# RheoBoard_V8.net
KiCad netlist of a schematic drawn in Altium Designer
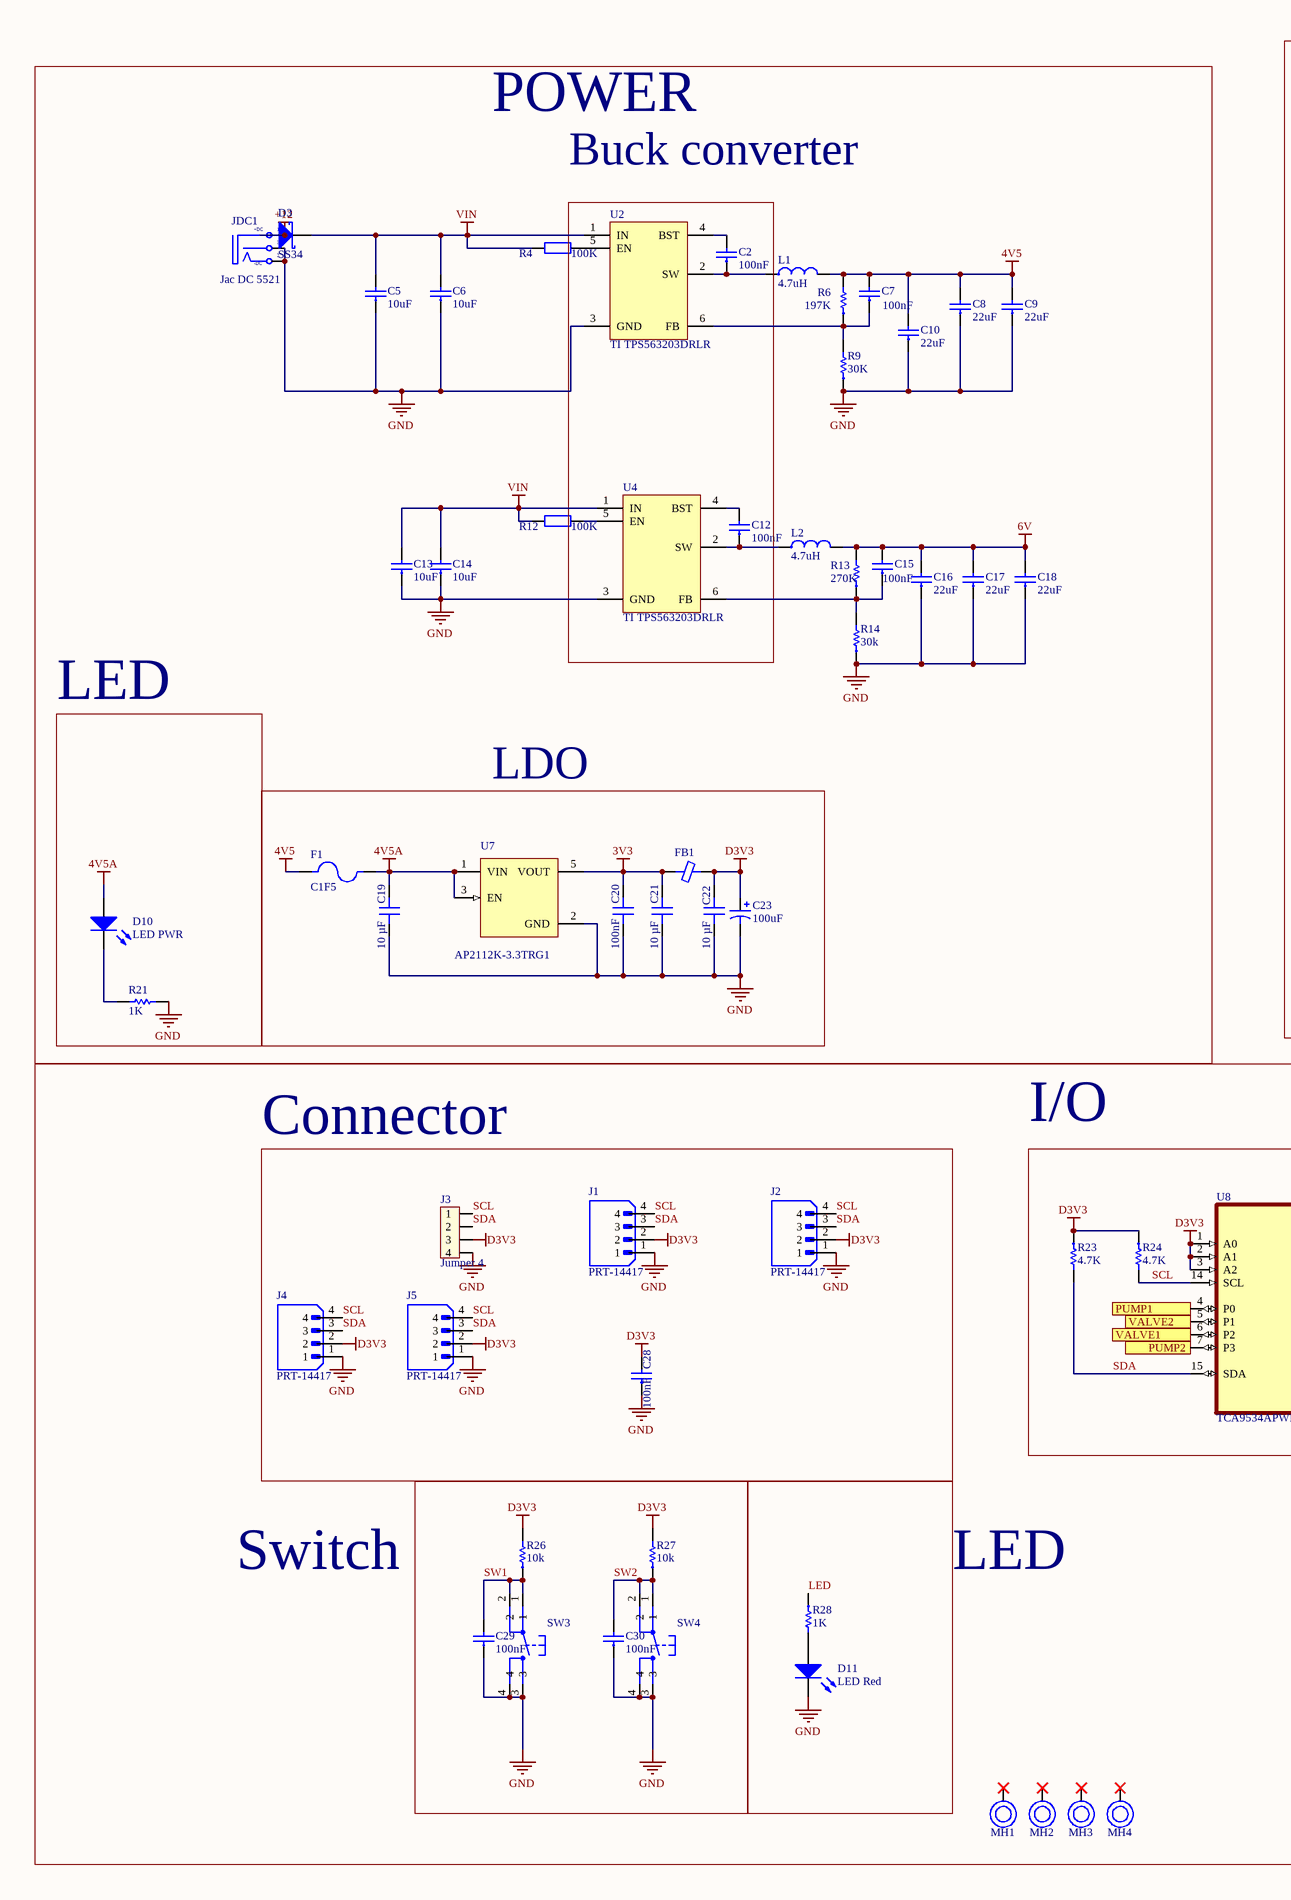
[diagram p0: RheoBoard_V8.SchDoc, left]
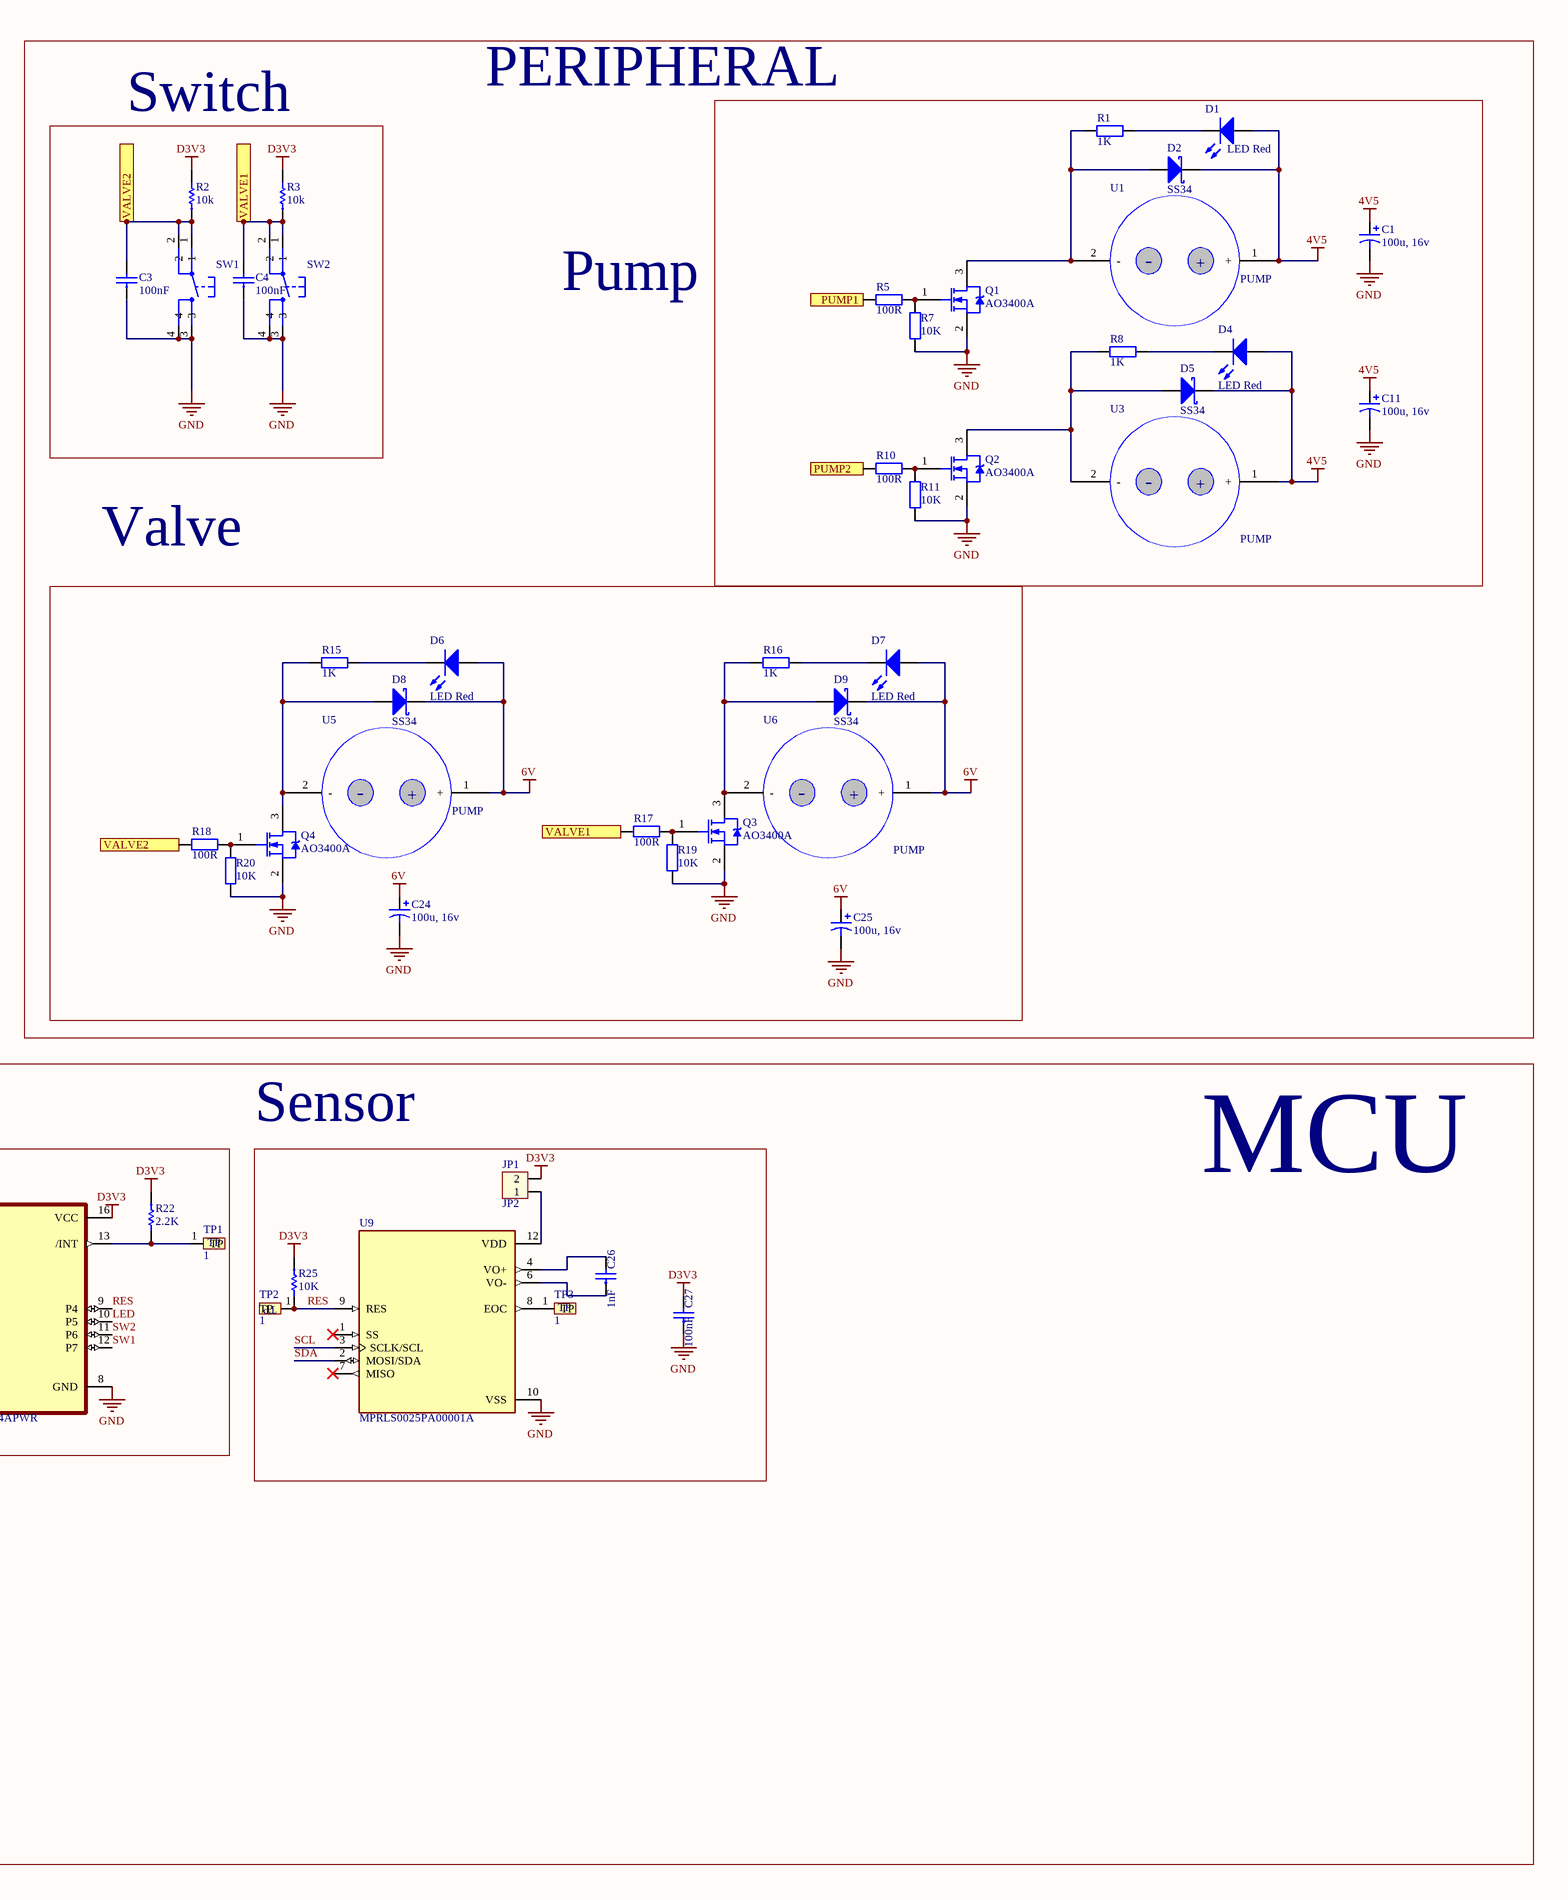
[diagram p1: RheoBoard_V8.SchDoc, right]

(export (version "E")
  (design (tool "Eeschema 10.0.6"))
  (components
    (comp (ref "C1")
      (value "100u, 16v")
      (footprint "CAPACITOR SIZE_D(D6.6)")
      (description "Nichicon Aluminum Cap 220uF 10V 20%")
      (fields (field (name "Comment") "CAP ALUM 100UF 20% 16V SMD"))
      (libsource (lib "capacitor") (part "UWT1C101MCL1GB"))
    )
    (comp (ref "C2")
      (value "100nF")
      (footprint "C0603")
      (description "CAP CER 100nF 10% 50V X7R 0603 SMD")
      (libsource (lib "2502-GMQLITE-MAIN") (part "CAPCER0001 100nF 10% 50V X7R 0603 SMD_1"))
    )
    (comp (ref "C3")
      (value "100nF")
      (footprint "C0603")
      (description "CAP CER 100nF 10% 50V X7R 0603 SMD")
      (libsource (lib "2502-GMQLITE-MAIN") (part "CAPCER0001 100nF 10% 50V X7R 0603 SMD"))
    )
    (comp (ref "C4")
      (value "100nF")
      (footprint "C0603")
      (description "CAP CER 100nF 10% 50V X7R 0603 SMD")
      (libsource (lib "2502-GMQLITE-MAIN") (part "CAPCER0001 100nF 10% 50V X7R 0603 SMD"))
    )
    (comp (ref "C5")
      (value "10uF")
      (footprint "CN-SMD-0603")
      (description "CAP CER 10uF 20% 6.3V X5R 0402 SMD")
      (libsource (lib "2502-GMQLITE-MAIN") (part "CAPCER0040 10uF 20% 6.3V X5R 0402 SMD"))
    )
    (comp (ref "C6")
      (value "10uF")
      (footprint "CN-SMD-0603")
      (description "CAP CER 10uF 20% 6.3V X5R 0402 SMD")
      (libsource (lib "2502-GMQLITE-MAIN") (part "CAPCER0040 10uF 20% 6.3V X5R 0402 SMD"))
    )
    (comp (ref "C7")
      (value "100nF")
      (footprint "C0603")
      (description "CAP CER 100nF 10% 50V X7R 0603 SMD")
      (libsource (lib "2502-GMQLITE-MAIN") (part "CAPCER0001 100nF 10% 50V X7R 0603 SMD"))
    )
    (comp (ref "C8")
      (value "22uF")
      (footprint "CN-SMD-0603")
      (description "CAP CER 10uF 20% 6.3V X5R 0402 SMD")
      (libsource (lib "2502-GMQLITE-MAIN") (part "CAPCER0040 10uF 20% 6.3V X5R 0402 SMD"))
    )
    (comp (ref "C9")
      (value "22uF")
      (footprint "CN-SMD-0603")
      (description "CAP CER 10uF 20% 6.3V X5R 0402 SMD")
      (libsource (lib "2502-GMQLITE-MAIN") (part "CAPCER0040 10uF 20% 6.3V X5R 0402 SMD"))
    )
    (comp (ref "C10")
      (value "22uF")
      (footprint "CN-SMD-0603")
      (description "CAP CER 10uF 20% 6.3V X5R 0402 SMD")
      (libsource (lib "2502-GMQLITE-MAIN") (part "CAPCER0040 10uF 20% 6.3V X5R 0402 SMD"))
    )
    (comp (ref "C11")
      (value "100u, 16v")
      (footprint "CAPACITOR SIZE_D(D6.6)")
      (description "Nichicon Aluminum Cap 220uF 10V 20%")
      (fields (field (name "Comment") "CAP ALUM 100UF 20% 16V SMD"))
      (libsource (lib "capacitor") (part "UWT1C101MCL1GB"))
    )
    (comp (ref "C12")
      (value "100nF")
      (footprint "C0603")
      (description "CAP CER 100nF 10% 50V X7R 0603 SMD")
      (libsource (lib "2502-GMQLITE-MAIN") (part "CAPCER0001 100nF 10% 50V X7R 0603 SMD_1"))
    )
    (comp (ref "C13")
      (value "10uF")
      (footprint "CN-SMD-0603")
      (description "CAP CER 10uF 20% 6.3V X5R 0402 SMD")
      (libsource (lib "2502-GMQLITE-MAIN") (part "CAPCER0040 10uF 20% 6.3V X5R 0402 SMD"))
    )
    (comp (ref "C14")
      (value "10uF")
      (footprint "CN-SMD-0603")
      (description "CAP CER 10uF 20% 6.3V X5R 0402 SMD")
      (libsource (lib "2502-GMQLITE-MAIN") (part "CAPCER0040 10uF 20% 6.3V X5R 0402 SMD"))
    )
    (comp (ref "C15")
      (value "100nF")
      (footprint "C0603")
      (description "CAP CER 100nF 10% 50V X7R 0603 SMD")
      (libsource (lib "2502-GMQLITE-MAIN") (part "CAPCER0001 100nF 10% 50V X7R 0603 SMD"))
    )
    (comp (ref "C16")
      (value "22uF")
      (footprint "CN-SMD-0603")
      (description "CAP CER 10uF 20% 6.3V X5R 0402 SMD")
      (libsource (lib "2502-GMQLITE-MAIN") (part "CAPCER0040 10uF 20% 6.3V X5R 0402 SMD"))
    )
    (comp (ref "C17")
      (value "22uF")
      (footprint "CN-SMD-0603")
      (description "CAP CER 10uF 20% 6.3V X5R 0402 SMD")
      (libsource (lib "2502-GMQLITE-MAIN") (part "CAPCER0040 10uF 20% 6.3V X5R 0402 SMD"))
    )
    (comp (ref "C18")
      (value "22uF")
      (footprint "CN-SMD-0603")
      (description "CAP CER 10uF 20% 6.3V X5R 0402 SMD")
      (libsource (lib "2502-GMQLITE-MAIN") (part "CAPCER0040 10uF 20% 6.3V X5R 0402 SMD"))
    )
    (comp (ref "C19")
      (value "10 µF")
      (footprint "C0603")
      (description "CAP0603 X7R 10UF 10% 10V")
      (fields
        (field (name "PART NUMBER") "GMC10X7R106K10NT")
        (field (name "MANUFACTURER") "Cal-Chip Electronics, Inc.")
      )
      (libsource (lib "Celestial Altium Library - altium_library") (part "Capacitor"))
    )
    (comp (ref "C20")
      (value "100nF")
      (footprint "C0603")
      (description "CAP0603 X7R 10UF 10% 10V")
      (fields
        (field (name "PART NUMBER") "GMC10X7R106K10NT")
        (field (name "MANUFACTURER") "Cal-Chip Electronics, Inc.")
      )
      (libsource (lib "Celestial Altium Library - altium_library") (part "Capacitor"))
    )
    (comp (ref "C21")
      (value "10 µF")
      (footprint "C0603")
      (description "CAP0603 X7R 10UF 10% 10V")
      (fields
        (field (name "PART NUMBER") "GMC10X7R106K10NT")
        (field (name "MANUFACTURER") "Cal-Chip Electronics, Inc.")
      )
      (libsource (lib "Celestial Altium Library - altium_library") (part "Capacitor"))
    )
    (comp (ref "C22")
      (value "10 µF")
      (footprint "C0603")
      (description "CAP0603 X7R 10UF 10% 10V")
      (fields
        (field (name "PART NUMBER") "GMC10X7R106K10NT")
        (field (name "MANUFACTURER") "Cal-Chip Electronics, Inc.")
      )
      (libsource (lib "Celestial Altium Library - altium_library") (part "Capacitor"))
    )
    (comp (ref "C23")
      (value "100uF")
      (footprint "CAPACITOR SIZE_D(D6.6)")
      (description "Nichicon Aluminum Cap 220uF 10V 20%")
      (fields (field (name "Comment") "CAP ALUM 100UF 20% 16V SMD"))
      (libsource (lib "capacitor") (part "UWT1C101MCL1GB"))
    )
    (comp (ref "C24")
      (value "100u, 16v")
      (footprint "CAPACITOR SIZE_D(D6.6)")
      (description "Nichicon Aluminum Cap 220uF 10V 20%")
      (fields (field (name "Comment") "CAP ALUM 100UF 20% 16V SMD"))
      (libsource (lib "capacitor") (part "UWT1C101MCL1GB"))
    )
    (comp (ref "C25")
      (value "100u, 16v")
      (footprint "CAPACITOR SIZE_D(D6.6)")
      (description "Nichicon Aluminum Cap 220uF 10V 20%")
      (fields (field (name "Comment") "CAP ALUM 100UF 20% 16V SMD"))
      (libsource (lib "capacitor") (part "UWT1C101MCL1GB"))
    )
    (comp (ref "C26")
      (value "1nF")
      (footprint "C0603")
      (description "CAP CER 100nF 10% 50V X7R 0603 SMD")
      (libsource (lib "2502-GMQLITE-MAIN") (part "CAPCER0001 100nF 10% 50V X7R 0603 SMD"))
    )
    (comp (ref "C27")
      (value "100nF")
      (footprint "C0603")
      (description "CAP CER 100nF 10% 50V X7R 0603 SMD")
      (libsource (lib "2502-GMQLITE-MAIN") (part "CAPCER0001 100nF 10% 50V X7R 0603 SMD"))
    )
    (comp (ref "C28")
      (value "100nF")
      (footprint "C0603")
      (description "CAP CER 100nF 10% 50V X7R 0603 SMD")
      (libsource (lib "2502-GMQLITE-MAIN") (part "CAPCER0001 100nF 10% 50V X7R 0603 SMD"))
    )
    (comp (ref "C29")
      (value "100nF")
      (footprint "C0603")
      (description "CAP CER 100nF 10% 50V X7R 0603 SMD")
      (libsource (lib "2502-GMQLITE-MAIN") (part "CAPCER0001 100nF 10% 50V X7R 0603 SMD"))
    )
    (comp (ref "C30")
      (value "100nF")
      (footprint "C0603")
      (description "CAP CER 100nF 10% 50V X7R 0603 SMD")
      (libsource (lib "2502-GMQLITE-MAIN") (part "CAPCER0001 100nF 10% 50V X7R 0603 SMD"))
    )
    (comp (ref "D1")
      (value "LED Red")
      (footprint "LED0603-R")
      (description "Lite-On LED Red 0603")
      (libsource (lib "diode") (part "LTST-C190KRKT"))
    )
    (comp (ref "D2")
      (value "SS34")
      (footprint "DO-214AC")
      (description "Schottky Diode 40V 3A SMA")
      (libsource (lib "diode") (part "SS34"))
    )
    (comp (ref "D3")
      (value "SS34")
      (footprint "DO-214AC")
      (description "Schottky Diode 40V 3A SMA")
      (libsource (lib "diode") (part "SS34"))
    )
    (comp (ref "D4")
      (value "LED Red")
      (footprint "LED0603-R")
      (description "Lite-On LED Red 0603")
      (libsource (lib "diode") (part "LTST-C190KRKT"))
    )
    (comp (ref "D5")
      (value "SS34")
      (footprint "DO-214AC")
      (description "Schottky Diode 40V 3A SMA")
      (libsource (lib "diode") (part "SS34"))
    )
    (comp (ref "D6")
      (value "LED Red")
      (footprint "LED0603-R")
      (description "Lite-On LED Red 0603")
      (libsource (lib "diode") (part "LTST-C190KRKT"))
    )
    (comp (ref "D7")
      (value "LED Red")
      (footprint "LED0603-R")
      (description "Lite-On LED Red 0603")
      (libsource (lib "diode") (part "LTST-C190KRKT"))
    )
    (comp (ref "D8")
      (value "SS34")
      (footprint "DO-214AC")
      (description "Schottky Diode 40V 3A SMA")
      (libsource (lib "diode") (part "SS34"))
    )
    (comp (ref "D9")
      (value "SS34")
      (footprint "DO-214AC")
      (description "Schottky Diode 40V 3A SMA")
      (libsource (lib "diode") (part "SS34"))
    )
    (comp (ref "D10")
      (value "LED PWR")
      (footprint "LED0603-R")
      (description "Lite-On LED Red 0603")
      (fields (field (name "Comment") "LED Red"))
      (libsource (lib "diode") (part "LTST-C190KRKT"))
    )
    (comp (ref "D11")
      (value "LED Red")
      (footprint "LED0603-R")
      (description "Lite-On LED Red 0603")
      (libsource (lib "diode") (part "LTST-C190KRKT"))
    )
    (comp (ref "F1")
      (value "C1F5")
      (footprint "FUSE C1F5")
      (description "Fuse Chip Fast Acting 5A 125V SMD Solder Pad 1206 3.2 X 1.58 X 0.63mm")
      (fields (field (name "MANUFACTURER") "Bel TRP"))
      (libsource (lib "POWER_PIN_CAMERA") (part "C1F5"))
    )
    (comp (ref "FB1")
      (value "330 Ohms @ 100 MHz")
      (footprint "L0603")
      (description "FERRITE BEAD 330 OHM 0603 1LN")
      (fields
        (field (name "PART NUMBER") "BLM18KG331SH1D")
        (field (name "MANUFACTURER") "Murata Electronics")
      )
      (libsource (lib "Celestial Altium Library - altium_library") (part "Ferrite Chip"))
    )
    (comp (ref "J1")
      (value "PRT-14417")
      (footprint "SPARKFUN_PRT-14417")
      (description "QWIIC JST CONNECTOR - SMD 4-PIN")
      (fields (field (name "MF") "SparkFun Electronics"))
      (libsource (lib "PRT-14417") (part "PRT-14417"))
    )
    (comp (ref "J2")
      (value "PRT-14417")
      (footprint "SPARKFUN_PRT-14417")
      (description "QWIIC JST CONNECTOR - SMD 4-PIN")
      (fields (field (name "MF") "SparkFun Electronics"))
      (libsource (lib "PRT-14417") (part "PRT-14417"))
    )
    (comp (ref "J3")
      (value "Jumper 4")
      (footprint "JP4")
      (description "Jumper 3")
      (libsource (lib "hanguyen") (part "JP4"))
    )
    (comp (ref "J4")
      (value "PRT-14417")
      (footprint "SPARKFUN_PRT-14417")
      (description "QWIIC JST CONNECTOR - SMD 4-PIN")
      (fields (field (name "MF") "SparkFun Electronics"))
      (libsource (lib "PRT-14417") (part "PRT-14417"))
    )
    (comp (ref "J5")
      (value "PRT-14417")
      (footprint "SPARKFUN_PRT-14417")
      (description "QWIIC JST CONNECTOR - SMD 4-PIN")
      (fields (field (name "MF") "SparkFun Electronics"))
      (libsource (lib "PRT-14417") (part "PRT-14417"))
    )
    (comp (ref "JDC1")
      (value "Jac DC 5521")
      (footprint "DC0")
      (description "Jac DC input")
      (libsource (lib "2502-GMQLITE-MAIN") (part "DCIN"))
    )
    (comp (ref "JP1")
      (value "JP2")
      (footprint "CON2")
      (description "Connector 2")
      (libsource (lib "hanguyen") (part "Con2"))
    )
    (comp (ref "L1")
      (value "4.7uH")
      (footprint "IND-0420-2R2")
      (description "IND MOI 1W2T 2.2uH 20% 5A 0420 SMD")
      (libsource (lib "2502-GMQLITE-MAIN") (part "INDMOI0016 1W2T 2.2uH 20% 5A 0420 SMD"))
    )
    (comp (ref "L2")
      (value "4.7uH")
      (footprint "IND-0420-2R2")
      (description "IND MOI 1W2T 2.2uH 20% 5A 0420 SMD")
      (libsource (lib "2502-GMQLITE-MAIN") (part "INDMOI0016 1W2T 2.2uH 20% 5A 0420 SMD"))
    )
    (comp (ref "MH1") (value "MOUNTING HOLE") (footprint "M3") (libsource (lib "INVERTER") (part "MH")))
    (comp (ref "MH2") (value "MOUNTING HOLE") (footprint "M3") (libsource (lib "INVERTER") (part "MH")))
    (comp (ref "MH3") (value "MOUNTING HOLE") (footprint "M3") (libsource (lib "INVERTER") (part "MH")))
    (comp (ref "MH4") (value "MOUNTING HOLE") (footprint "M3") (libsource (lib "INVERTER") (part "MH")))
    (comp (ref "Q1")
      (value "AO3400A")
      (footprint "SOT-23")
      (description "MOSFET N-CH 25V 5.8A SOT23")
      (libsource (lib "fet") (part "IRFML8244TRPBF"))
    )
    (comp (ref "Q2")
      (value "AO3400A")
      (footprint "SOT-23")
      (description "MOSFET N-CH 25V 5.8A SOT23")
      (libsource (lib "fet") (part "IRFML8244TRPBF"))
    )
    (comp (ref "Q3")
      (value "AO3400A")
      (footprint "SOT-23")
      (description "MOSFET N-CH 25V 5.8A SOT23")
      (libsource (lib "fet") (part "IRFML8244TRPBF"))
    )
    (comp (ref "Q4")
      (value "AO3400A")
      (footprint "SOT-23")
      (description "MOSFET N-CH 25V 5.8A SOT23")
      (libsource (lib "fet") (part "IRFML8244TRPBF"))
    )
    (comp (ref "R1")
      (value "1K")
      (footprint "R0603")
      (description "Yageo RES 1K 5% 1/10W 0603")
      (fields (field (name "Comment") "RES 1K 5% 1/10W 0603"))
      (libsource (lib "resistor") (part "RC0603JR-071KL"))
    )
    (comp (ref "R2")
      (value "10k")
      (footprint "R0603")
      (description "RES CHP 8K4 1% 1/10W 0603 SMD")
      (libsource (lib "2502-GMQLITE-MAIN") (part "RESCHP0428 8K4 1% 0603 SMD"))
    )
    (comp (ref "R3")
      (value "10k")
      (footprint "R0603")
      (description "RES CHP 8K4 1% 1/10W 0603 SMD")
      (libsource (lib "2502-GMQLITE-MAIN") (part "RESCHP0428 8K4 1% 0603 SMD"))
    )
    (comp (ref "R4")
      (value "100K")
      (footprint "R0603")
      (description "Yageo RES 100K 5% 1/10W 0603")
      (fields (field (name "Comment") "RES 100K 5% 1/10W 0603"))
      (libsource (lib "resistor") (part "RC0603JR-07100KL"))
    )
    (comp (ref "R5")
      (value "100R")
      (footprint "R0603")
      (description "Yageo RES 100R 5% 1/10W 0603")
      (fields (field (name "Comment") "RES 100R 5% 1/10W 0603"))
      (libsource (lib "resistor") (part "RC0603JR-07100RL"))
    )
    (comp (ref "R6")
      (value "197K")
      (footprint "R0603")
      (description "RES CHP 2K7 1% 1/10W 0603 SMD")
      (libsource (lib "2502-GMQLITE-MAIN") (part "RESCHP0195 2K7 1% 0603 SMD"))
    )
    (comp (ref "R7")
      (value "10K")
      (footprint "R0603")
      (description "Yageo RES 10K 5% 1/10W 0603")
      (fields (field (name "Comment") "RES 10K 5% 1/10W 0603"))
      (libsource (lib "resistor") (part "RC0603JR-0710KL"))
    )
    (comp (ref "R8")
      (value "1K")
      (footprint "R0603")
      (description "Yageo RES 1K 5% 1/10W 0603")
      (fields (field (name "Comment") "RES 1K 5% 1/10W 0603"))
      (libsource (lib "resistor") (part "RC0603JR-071KL"))
    )
    (comp (ref "R9")
      (value "30K")
      (footprint "R0603")
      (description "RES CHP 2K7 1% 1/10W 0603 SMD")
      (libsource (lib "2502-GMQLITE-MAIN") (part "RESCHP0195 2K7 1% 0603 SMD"))
    )
    (comp (ref "R10")
      (value "100R")
      (footprint "R0603")
      (description "Yageo RES 100R 5% 1/10W 0603")
      (fields (field (name "Comment") "RES 100R 5% 1/10W 0603"))
      (libsource (lib "resistor") (part "RC0603JR-07100RL"))
    )
    (comp (ref "R11")
      (value "10K")
      (footprint "R0603")
      (description "Yageo RES 10K 5% 1/10W 0603")
      (fields (field (name "Comment") "RES 10K 5% 1/10W 0603"))
      (libsource (lib "resistor") (part "RC0603JR-0710KL"))
    )
    (comp (ref "R12")
      (value "100K")
      (footprint "R0603")
      (description "Yageo RES 100K 5% 1/10W 0603")
      (fields (field (name "Comment") "RES 100K 5% 1/10W 0603"))
      (libsource (lib "resistor") (part "RC0603JR-07100KL"))
    )
    (comp (ref "R13")
      (value "270K")
      (footprint "R0603")
      (description "RES CHP 2K7 1% 1/10W 0603 SMD")
      (libsource (lib "2502-GMQLITE-MAIN") (part "RESCHP0195 2K7 1% 0603 SMD"))
    )
    (comp (ref "R14")
      (value "30k")
      (footprint "R0603")
      (description "RES CHP 2K7 1% 1/10W 0603 SMD")
      (libsource (lib "2502-GMQLITE-MAIN") (part "RESCHP0195 2K7 1% 0603 SMD"))
    )
    (comp (ref "R15")
      (value "1K")
      (footprint "R0603")
      (description "Yageo RES 1K 5% 1/10W 0603")
      (fields (field (name "Comment") "RES 1K 5% 1/10W 0603"))
      (libsource (lib "resistor") (part "RC0603JR-071KL"))
    )
    (comp (ref "R16")
      (value "1K")
      (footprint "R0603")
      (description "Yageo RES 1K 5% 1/10W 0603")
      (fields (field (name "Comment") "RES 1K 5% 1/10W 0603"))
      (libsource (lib "resistor") (part "RC0603JR-071KL"))
    )
    (comp (ref "R17")
      (value "100R")
      (footprint "R0603")
      (description "Yageo RES 100R 5% 1/10W 0603")
      (fields (field (name "Comment") "RES 100R 5% 1/10W 0603"))
      (libsource (lib "resistor") (part "RC0603JR-07100RL"))
    )
    (comp (ref "R18")
      (value "100R")
      (footprint "R0603")
      (description "Yageo RES 100R 5% 1/10W 0603")
      (fields (field (name "Comment") "RES 100R 5% 1/10W 0603"))
      (libsource (lib "resistor") (part "RC0603JR-07100RL"))
    )
    (comp (ref "R19")
      (value "10K")
      (footprint "R0603")
      (description "Yageo RES 10K 5% 1/10W 0603")
      (fields (field (name "Comment") "RES 10K 5% 1/10W 0603"))
      (libsource (lib "resistor") (part "RC0603JR-0710KL"))
    )
    (comp (ref "R20")
      (value "10K")
      (footprint "R0603")
      (description "Yageo RES 10K 5% 1/10W 0603")
      (fields (field (name "Comment") "RES 10K 5% 1/10W 0603"))
      (libsource (lib "resistor") (part "RC0603JR-0710KL"))
    )
    (comp (ref "R21")
      (value "1K")
      (footprint "R0603")
      (description "Res Thick Film 0603 2.2K Ohm 5% 1/10W ±200ppm/°C Molded SMD SMD Paper T/R")
      (fields
        (field (name "MANUFACTURER") "Vishay")
        (field (name "MANUFACTURER PART NUMBER") "CRCW06032K20JNEA")
      )
      (libsource (lib "Stm32_Flyback_Driver_250814_1") (part "Resistor 2.2K"))
    )
    (comp (ref "R22")
      (value "2.2K")
      (footprint "R0603")
      (description "RES CHP 8K4 1% 1/10W 0603 SMD")
      (libsource (lib "2502-GMQLITE-MAIN") (part "RESCHP0428 8K4 1% 0603 SMD"))
    )
    (comp (ref "R23")
      (value "4.7K")
      (footprint "R0603")
      (description "RES CHP 8K4 1% 1/10W 0603 SMD")
      (libsource (lib "2502-GMQLITE-MAIN") (part "RESCHP0428 8K4 1% 0603 SMD"))
    )
    (comp (ref "R24")
      (value "4.7K")
      (footprint "R0603")
      (description "RES CHP 8K4 1% 1/10W 0603 SMD")
      (libsource (lib "2502-GMQLITE-MAIN") (part "RESCHP0428 8K4 1% 0603 SMD"))
    )
    (comp (ref "R25")
      (value "10K")
      (footprint "R0603")
      (description "RES CHP 8K4 1% 1/10W 0603 SMD")
      (libsource (lib "2502-GMQLITE-MAIN") (part "RESCHP0428 8K4 1% 0603 SMD"))
    )
    (comp (ref "R26")
      (value "10k")
      (footprint "R0603")
      (description "RES CHP 8K4 1% 1/10W 0603 SMD")
      (libsource (lib "2502-GMQLITE-MAIN") (part "RESCHP0428 8K4 1% 0603 SMD"))
    )
    (comp (ref "R27")
      (value "10k")
      (footprint "R0603")
      (description "RES CHP 8K4 1% 1/10W 0603 SMD")
      (libsource (lib "2502-GMQLITE-MAIN") (part "RESCHP0428 8K4 1% 0603 SMD"))
    )
    (comp (ref "R28")
      (value "1K")
      (footprint "R0603")
      (description "RES CHP 8K4 1% 1/10W 0603 SMD")
      (libsource (lib "2502-GMQLITE-MAIN") (part "RESCHP0428 8K4 1% 0603 SMD"))
    )
    (comp (ref "SW1")
      (value "SW2")
      (footprint "SWITCH")
      (description "Switch button 4 pin")
      (libsource (lib "Stm32_Flyback_Driver_250814_1") (part "SW2"))
    )
    (comp (ref "SW2")
      (value "SW2")
      (footprint "SWITCH")
      (description "Switch button 4 pin")
      (libsource (lib "Stm32_Flyback_Driver_250814_1") (part "SW2"))
    )
    (comp (ref "SW3")
      (value "SW2")
      (footprint "SWITCH")
      (description "Switch button 4 pin")
      (libsource (lib "Stm32_Flyback_Driver_250814_1") (part "SW2"))
    )
    (comp (ref "SW4")
      (value "SW2")
      (footprint "SWITCH")
      (description "Switch button 4 pin")
      (libsource (lib "Stm32_Flyback_Driver_250814_1") (part "SW2"))
    )
    (comp (ref "TP1")
      (value "1")
      (footprint "TP")
      (description "CONNECT 1")
      (libsource (lib "") (part "TP_1"))
    )
    (comp (ref "TP2")
      (value "1")
      (footprint "TP")
      (description "CONNECT 1")
      (libsource (lib "hanguyen") (part "TP"))
    )
    (comp (ref "TP3")
      (value "1")
      (footprint "TP")
      (description "CONNECT 1")
      (libsource (lib "") (part "TP_1"))
    )
    (comp (ref "U1")
      (value "PUMP")
      (footprint "Pump")
      (description "Connector Header 2 Position 6.35mm Solder Straight Thru-Hole 2 Terminal 1 Port MLX-Series")
      (fields (field (name "MANUFACTURER") "Molex") (field (name "MANUFACTURER PART NUMBER") "10-84-4022"))
      (libsource (lib "LIB_PRESSURE") (part "A5F083"))
    )
    (comp (ref "U2")
      (value "TI TPS563203DRLR")
      (footprint "SOT50P160X60-6N")
      (description "ICS OCV BCK TPS563201 3A SOT23-6 SMD")
      (libsource (lib "2502-GMQLITE-MAIN") (part "ICSOCV0021 BCK TPS563201 3A SOT23-6 SMD"))
    )
    (comp (ref "U3")
      (value "PUMP")
      (footprint "Pump")
      (description "Connector Header 2 Position 6.35mm Solder Straight Thru-Hole 2 Terminal 1 Port MLX-Series")
      (fields (field (name "MANUFACTURER") "Molex") (field (name "MANUFACTURER PART NUMBER") "10-84-4022"))
      (libsource (lib "LIB_PRESSURE") (part "A5F083"))
    )
    (comp (ref "U4")
      (value "TI TPS563203DRLR")
      (footprint "SOT50P160X60-6N")
      (description "ICS OCV BCK TPS563201 3A SOT23-6 SMD")
      (libsource (lib "2502-GMQLITE-MAIN") (part "ICSOCV0021 BCK TPS563201 3A SOT23-6 SMD"))
    )
    (comp (ref "U5")
      (value "PUMP")
      (footprint "Pump")
      (description "Connector Header 2 Position 6.35mm Solder Straight Thru-Hole 2 Terminal 1 Port MLX-Series")
      (fields (field (name "MANUFACTURER") "Molex") (field (name "MANUFACTURER PART NUMBER") "10-84-4022"))
      (libsource (lib "LIB_PRESSURE") (part "A5F083"))
    )
    (comp (ref "U6")
      (value "PUMP")
      (footprint "Pump")
      (description "Connector Header 2 Position 6.35mm Solder Straight Thru-Hole 2 Terminal 1 Port MLX-Series")
      (fields (field (name "MANUFACTURER") "Molex") (field (name "MANUFACTURER PART NUMBER") "10-84-4022"))
      (libsource (lib "LIB_PRESSURE") (part "A5F083"))
    )
    (comp (ref "U7")
      (value "AP2112K-3.3TRG1")
      (footprint "SOT-23-5")
      (description "AP2112 Series 0.6 A 3.3 V Fixed Output SMT LDO Linear Regulator - SOT23-5")
      (fields (field (name "MF") "Diodes Inc."))
      (libsource (lib "hanguyen") (part "AP2112K-3.3TRG1"))
    )
    (comp (ref "U8")
      (value "TCA9534APWR")
      (footprint "SOP65P640X120-16N")
      (description "8-bit 1.65- to 5.5-V I2C/SMBus I/O expander with interrupt, & config registers")
      (fields (field (name "MF") "Texas Instruments"))
      (libsource (lib "TCA9534APWR") (part "TCA9534APWR"))
    )
    (comp (ref "U9")
      (value "MPRLS0025PA00001A")
      (footprint "SnapEDApcb:XDCR_MPRLS0025PA00001A")
      (description "Pressure Sensor 25PSI _172.37kPa_ Absolute Male - 0.1 _2.5mm_ Tube 24 b 12-SMD Module")
      (fields (field (name "DIGI-KEY_PART_NUMBER") "480-7098-1-ND") (field (name "MF") "Honeywell Sensing"))
      (libsource (lib "SnapEDAsch") (part "MPRLS0025PA00001A"))
    )
  )
  (nets
    (net (code "1") (name "+12") (class "Default")
      (node (ref "D3") (pin "1") (pinfunction "A_1") (pintype "passive"))
      (node (ref "JDC1") (pin "1") (pinfunction "T_1") (pintype "passive"))
    )
    (net (code "2") (name "/LED") (class "Default")
      (node (ref "R28") (pin "1") (pinfunction "1_1") (pintype "passive"))
      (node (ref "U8") (pin "10") (pinfunction "P5_10") (pintype "bidirectional"))
    )
    (net (code "3") (name "/PUMP1") (class "Default")
      (node (ref "R5") (pin "1") (pinfunction "1_1") (pintype "passive"))
      (node (ref "U8") (pin "4") (pinfunction "P0_4") (pintype "bidirectional"))
    )
    (net (code "4") (name "/PUMP2") (class "Default")
      (node (ref "R10") (pin "1") (pinfunction "1_1") (pintype "passive"))
      (node (ref "U8") (pin "7") (pinfunction "P3_7") (pintype "bidirectional"))
    )
    (net (code "5") (name "/RES") (class "Default")
      (node (ref "R25") (pin "2") (pinfunction "2_2") (pintype "passive"))
      (node (ref "TP2") (pin "1") (pinfunction "TP_1") (pintype "passive"))
      (node (ref "U8") (pin "9") (pinfunction "P4_9") (pintype "bidirectional"))
      (node (ref "U9") (pin "9") (pinfunction "RES_9") (pintype "input"))
    )
    (net (code "6") (name "/SCL") (class "Default")
      (node (ref "J1") (pin "4") (pinfunction "4_4") (pintype "passive"))
      (node (ref "J2") (pin "4") (pinfunction "4_4") (pintype "passive"))
      (node (ref "J3") (pin "1") (pinfunction "1_1") (pintype "passive"))
      (node (ref "J4") (pin "4") (pinfunction "4_4") (pintype "passive"))
      (node (ref "J5") (pin "4") (pinfunction "4_4") (pintype "passive"))
      (node (ref "R24") (pin "2") (pinfunction "2_2") (pintype "passive"))
      (node (ref "U8") (pin "14") (pinfunction "SCL_14") (pintype "input"))
      (node (ref "U9") (pin "3") (pinfunction "SCLK/SCL_3") (pintype "input"))
    )
    (net (code "7") (name "/SDA") (class "Default")
      (node (ref "J1") (pin "3") (pinfunction "3_3") (pintype "passive"))
      (node (ref "J2") (pin "3") (pinfunction "3_3") (pintype "passive"))
      (node (ref "J3") (pin "2") (pinfunction "2_2") (pintype "passive"))
      (node (ref "J4") (pin "3") (pinfunction "3_3") (pintype "passive"))
      (node (ref "J5") (pin "3") (pinfunction "3_3") (pintype "passive"))
      (node (ref "R23") (pin "2") (pinfunction "2_2") (pintype "passive"))
      (node (ref "U8") (pin "15") (pinfunction "SDA_15") (pintype "bidirectional"))
      (node (ref "U9") (pin "2") (pinfunction "MOSI/SDA_2") (pintype "bidirectional"))
    )
    (net (code "8") (name "/SW1") (class "Default")
      (node (ref "C29") (pin "2") (pinfunction "2_2") (pintype "passive"))
      (node (ref "R26") (pin "1") (pinfunction "1_1") (pintype "passive"))
      (node (ref "SW3") (pin "1") (pinfunction "1_1") (pintype "passive"))
      (node (ref "SW3") (pin "2") (pinfunction "2_2") (pintype "passive"))
      (node (ref "U8") (pin "12") (pinfunction "P7_12") (pintype "bidirectional"))
    )
    (net (code "9") (name "/SW2") (class "Default")
      (node (ref "C30") (pin "2") (pinfunction "2_2") (pintype "passive"))
      (node (ref "R27") (pin "1") (pinfunction "1_1") (pintype "passive"))
      (node (ref "SW4") (pin "1") (pinfunction "1_1") (pintype "passive"))
      (node (ref "SW4") (pin "2") (pinfunction "2_2") (pintype "passive"))
      (node (ref "U8") (pin "11") (pinfunction "P6_11") (pintype "bidirectional"))
    )
    (net (code "10") (name "/VALVE1") (class "Default")
      (node (ref "C4") (pin "2") (pinfunction "2_2") (pintype "passive"))
      (node (ref "R17") (pin "1") (pinfunction "1_1") (pintype "passive"))
      (node (ref "R3") (pin "1") (pinfunction "1_1") (pintype "passive"))
      (node (ref "SW2") (pin "1") (pinfunction "1_1") (pintype "passive"))
      (node (ref "SW2") (pin "2") (pinfunction "2_2") (pintype "passive"))
      (node (ref "U8") (pin "6") (pinfunction "P2_6") (pintype "bidirectional"))
    )
    (net (code "11") (name "/VALVE2") (class "Default")
      (node (ref "C3") (pin "2") (pinfunction "2_2") (pintype "passive"))
      (node (ref "R18") (pin "1") (pinfunction "1_1") (pintype "passive"))
      (node (ref "R2") (pin "1") (pinfunction "1_1") (pintype "passive"))
      (node (ref "SW1") (pin "1") (pinfunction "1_1") (pintype "passive"))
      (node (ref "SW1") (pin "2") (pinfunction "2_2") (pintype "passive"))
      (node (ref "U8") (pin "5") (pinfunction "P1_5") (pintype "bidirectional"))
    )
    (net (code "12") (name "3V3") (class "Default")
      (node (ref "C20") (pin "2") (pinfunction "2_2") (pintype "passive"))
      (node (ref "C21") (pin "2") (pinfunction "2_2") (pintype "passive"))
      (node (ref "FB1") (pin "1") (pinfunction "1_1") (pintype "passive"))
      (node (ref "U7") (pin "5") (pinfunction "VOUT_5") (pintype "power_in"))
    )
    (net (code "13") (name "4V5") (class "Default")
      (node (ref "C1") (pin "1") (pinfunction "1_1") (pintype "passive"))
      (node (ref "C10") (pin "2") (pinfunction "2_2") (pintype "passive"))
      (node (ref "C11") (pin "1") (pinfunction "1_1") (pintype "passive"))
      (node (ref "C7") (pin "2") (pinfunction "2_2") (pintype "passive"))
      (node (ref "C8") (pin "2") (pinfunction "2_2") (pintype "passive"))
      (node (ref "C9") (pin "2") (pinfunction "2_2") (pintype "passive"))
      (node (ref "D1") (pin "1") (pinfunction "A_1") (pintype "passive"))
      (node (ref "D2") (pin "2") (pinfunction "K_2") (pintype "passive"))
      (node (ref "D4") (pin "1") (pinfunction "A_1") (pintype "passive"))
      (node (ref "D5") (pin "2") (pinfunction "K_2") (pintype "passive"))
      (node (ref "F1") (pin "1") (pinfunction "1_1") (pintype "passive"))
      (node (ref "L1") (pin "2") (pinfunction "2_2") (pintype "passive"))
      (node (ref "R6") (pin "2") (pinfunction "2_2") (pintype "passive"))
      (node (ref "U1") (pin "1") (pinfunction "+_1") (pintype "passive"))
      (node (ref "U3") (pin "1") (pinfunction "+_1") (pintype "passive"))
    )
    (net (code "14") (name "4V5A") (class "Default")
      (node (ref "C19") (pin "2") (pinfunction "2_2") (pintype "passive"))
      (node (ref "D10") (pin "1") (pinfunction "A_1") (pintype "passive"))
      (node (ref "F1") (pin "2") (pinfunction "2_2") (pintype "passive"))
      (node (ref "U7") (pin "1") (pinfunction "VIN_1") (pintype "power_in"))
      (node (ref "U7") (pin "3") (pinfunction "EN_3") (pintype "input"))
    )
    (net (code "15") (name "6V") (class "Default")
      (node (ref "C15") (pin "2") (pinfunction "2_2") (pintype "passive"))
      (node (ref "C16") (pin "2") (pinfunction "2_2") (pintype "passive"))
      (node (ref "C17") (pin "2") (pinfunction "2_2") (pintype "passive"))
      (node (ref "C18") (pin "2") (pinfunction "2_2") (pintype "passive"))
      (node (ref "C24") (pin "1") (pinfunction "1_1") (pintype "passive"))
      (node (ref "C25") (pin "1") (pinfunction "1_1") (pintype "passive"))
      (node (ref "D6") (pin "1") (pinfunction "A_1") (pintype "passive"))
      (node (ref "D7") (pin "1") (pinfunction "A_1") (pintype "passive"))
      (node (ref "D8") (pin "2") (pinfunction "K_2") (pintype "passive"))
      (node (ref "D9") (pin "2") (pinfunction "K_2") (pintype "passive"))
      (node (ref "L2") (pin "2") (pinfunction "2_2") (pintype "passive"))
      (node (ref "R13") (pin "2") (pinfunction "2_2") (pintype "passive"))
      (node (ref "U5") (pin "1") (pinfunction "+_1") (pintype "passive"))
      (node (ref "U6") (pin "1") (pinfunction "+_1") (pintype "passive"))
    )
    (net (code "16") (name "D3V3") (class "Default")
      (node (ref "C22") (pin "2") (pinfunction "2_2") (pintype "passive"))
      (node (ref "C23") (pin "1") (pinfunction "1_1") (pintype "passive"))
      (node (ref "C27") (pin "2") (pinfunction "2_2") (pintype "passive"))
      (node (ref "C28") (pin "2") (pinfunction "2_2") (pintype "passive"))
      (node (ref "FB1") (pin "2") (pinfunction "2_2") (pintype "passive"))
      (node (ref "J1") (pin "2") (pinfunction "2_2") (pintype "passive"))
      (node (ref "J2") (pin "2") (pinfunction "2_2") (pintype "passive"))
      (node (ref "J3") (pin "3") (pinfunction "3_3") (pintype "passive"))
      (node (ref "J4") (pin "2") (pinfunction "2_2") (pintype "passive"))
      (node (ref "J5") (pin "2") (pinfunction "2_2") (pintype "passive"))
      (node (ref "JP1") (pin "2") (pinfunction "2_2") (pintype "passive"))
      (node (ref "R2") (pin "2") (pinfunction "2_2") (pintype "passive"))
      (node (ref "R22") (pin "1") (pinfunction "1_1") (pintype "passive"))
      (node (ref "R23") (pin "1") (pinfunction "1_1") (pintype "passive"))
      (node (ref "R24") (pin "1") (pinfunction "1_1") (pintype "passive"))
      (node (ref "R25") (pin "1") (pinfunction "1_1") (pintype "passive"))
      (node (ref "R26") (pin "2") (pinfunction "2_2") (pintype "passive"))
      (node (ref "R27") (pin "2") (pinfunction "2_2") (pintype "passive"))
      (node (ref "R3") (pin "2") (pinfunction "2_2") (pintype "passive"))
      (node (ref "U8") (pin "1") (pinfunction "A0_1") (pintype "input"))
      (node (ref "U8") (pin "16") (pinfunction "VCC_16") (pintype "power_in"))
      (node (ref "U8") (pin "2") (pinfunction "A1_2") (pintype "input"))
      (node (ref "U8") (pin "3") (pinfunction "A2_3") (pintype "input"))
    )
    (net (code "17") (name "GND") (class "Default")
      (node (ref "C1") (pin "2") (pinfunction "2_2") (pintype "passive"))
      (node (ref "C10") (pin "1") (pinfunction "1_1") (pintype "passive"))
      (node (ref "C11") (pin "2") (pinfunction "2_2") (pintype "passive"))
      (node (ref "C13") (pin "1") (pinfunction "1_1") (pintype "passive"))
      (node (ref "C14") (pin "1") (pinfunction "1_1") (pintype "passive"))
      (node (ref "C16") (pin "1") (pinfunction "1_1") (pintype "passive"))
      (node (ref "C17") (pin "1") (pinfunction "1_1") (pintype "passive"))
      (node (ref "C18") (pin "1") (pinfunction "1_1") (pintype "passive"))
      (node (ref "C19") (pin "1") (pinfunction "1_1") (pintype "passive"))
      (node (ref "C20") (pin "1") (pinfunction "1_1") (pintype "passive"))
      (node (ref "C21") (pin "1") (pinfunction "1_1") (pintype "passive"))
      (node (ref "C22") (pin "1") (pinfunction "1_1") (pintype "passive"))
      (node (ref "C23") (pin "2") (pinfunction "2_2") (pintype "passive"))
      (node (ref "C24") (pin "2") (pinfunction "2_2") (pintype "passive"))
      (node (ref "C25") (pin "2") (pinfunction "2_2") (pintype "passive"))
      (node (ref "C27") (pin "1") (pinfunction "1_1") (pintype "passive"))
      (node (ref "C28") (pin "1") (pinfunction "1_1") (pintype "passive"))
      (node (ref "C29") (pin "1") (pinfunction "1_1") (pintype "passive"))
      (node (ref "C3") (pin "1") (pinfunction "1_1") (pintype "passive"))
      (node (ref "C30") (pin "1") (pinfunction "1_1") (pintype "passive"))
      (node (ref "C4") (pin "1") (pinfunction "1_1") (pintype "passive"))
      (node (ref "C5") (pin "1") (pinfunction "1_1") (pintype "passive"))
      (node (ref "C6") (pin "1") (pinfunction "1_1") (pintype "passive"))
      (node (ref "C8") (pin "1") (pinfunction "1_1") (pintype "passive"))
      (node (ref "C9") (pin "1") (pinfunction "1_1") (pintype "passive"))
      (node (ref "D11") (pin "2") (pinfunction "K_2") (pintype "passive"))
      (node (ref "J1") (pin "1") (pinfunction "1_1") (pintype "passive"))
      (node (ref "J2") (pin "1") (pinfunction "1_1") (pintype "passive"))
      (node (ref "J3") (pin "4") (pinfunction "4_4") (pintype "passive"))
      (node (ref "J4") (pin "1") (pinfunction "1_1") (pintype "passive"))
      (node (ref "J5") (pin "1") (pinfunction "1_1") (pintype "passive"))
      (node (ref "JDC1") (pin "2") (pinfunction "TN_2") (pintype "passive"))
      (node (ref "JDC1") (pin "3") (pinfunction "S_3") (pintype "power_in"))
      (node (ref "Q1") (pin "2") (pinfunction "S_2") (pintype "passive"))
      (node (ref "Q2") (pin "2") (pinfunction "S_2") (pintype "passive"))
      (node (ref "Q3") (pin "2") (pinfunction "S_2") (pintype "passive"))
      (node (ref "Q4") (pin "2") (pinfunction "S_2") (pintype "passive"))
      (node (ref "R11") (pin "1") (pinfunction "1_1") (pintype "passive"))
      (node (ref "R14") (pin "1") (pinfunction "1_1") (pintype "passive"))
      (node (ref "R19") (pin "1") (pinfunction "1_1") (pintype "passive"))
      (node (ref "R20") (pin "1") (pinfunction "1_1") (pintype "passive"))
      (node (ref "R21") (pin "2") (pinfunction "2_2") (pintype "passive"))
      (node (ref "R7") (pin "1") (pinfunction "1_1") (pintype "passive"))
      (node (ref "R9") (pin "1") (pinfunction "1_1") (pintype "passive"))
      (node (ref "SW1") (pin "3") (pinfunction "3_3") (pintype "passive"))
      (node (ref "SW1") (pin "4") (pinfunction "4_4") (pintype "passive"))
      (node (ref "SW2") (pin "3") (pinfunction "3_3") (pintype "passive"))
      (node (ref "SW2") (pin "4") (pinfunction "4_4") (pintype "passive"))
      (node (ref "SW3") (pin "3") (pinfunction "3_3") (pintype "passive"))
      (node (ref "SW3") (pin "4") (pinfunction "4_4") (pintype "passive"))
      (node (ref "SW4") (pin "3") (pinfunction "3_3") (pintype "passive"))
      (node (ref "SW4") (pin "4") (pinfunction "4_4") (pintype "passive"))
      (node (ref "U2") (pin "3") (pinfunction "GND_3") (pintype "power_in"))
      (node (ref "U4") (pin "3") (pinfunction "GND_3") (pintype "power_in"))
      (node (ref "U7") (pin "2") (pinfunction "GND_2") (pintype "power_in"))
      (node (ref "U8") (pin "8") (pinfunction "GND_8") (pintype "power_in"))
      (node (ref "U9") (pin "10") (pinfunction "VSS_10") (pintype "power_in"))
    )
    (net (code "18") (name "Net-(D1-K)") (class "Default")
      (node (ref "D1") (pin "2") (pinfunction "K_2") (pintype "passive"))
      (node (ref "R1") (pin "2") (pinfunction "2_2") (pintype "passive"))
    )
    (net (code "19") (name "Net-(D2-A)") (class "Default")
      (node (ref "D2") (pin "1") (pinfunction "A_1") (pintype "passive"))
      (node (ref "Q1") (pin "3") (pinfunction "D_3") (pintype "passive"))
      (node (ref "R1") (pin "1") (pinfunction "1_1") (pintype "passive"))
      (node (ref "U1") (pin "2") (pinfunction "-_2") (pintype "passive"))
    )
    (net (code "20") (name "Net-(D4-K)") (class "Default")
      (node (ref "D4") (pin "2") (pinfunction "K_2") (pintype "passive"))
      (node (ref "R8") (pin "2") (pinfunction "2_2") (pintype "passive"))
    )
    (net (code "21") (name "Net-(D5-A)") (class "Default")
      (node (ref "D5") (pin "1") (pinfunction "A_1") (pintype "passive"))
      (node (ref "Q2") (pin "3") (pinfunction "D_3") (pintype "passive"))
      (node (ref "R8") (pin "1") (pinfunction "1_1") (pintype "passive"))
      (node (ref "U3") (pin "2") (pinfunction "-_2") (pintype "passive"))
    )
    (net (code "22") (name "Net-(D6-K)") (class "Default")
      (node (ref "D6") (pin "2") (pinfunction "K_2") (pintype "passive"))
      (node (ref "R15") (pin "2") (pinfunction "2_2") (pintype "passive"))
    )
    (net (code "23") (name "Net-(D7-K)") (class "Default")
      (node (ref "D7") (pin "2") (pinfunction "K_2") (pintype "passive"))
      (node (ref "R16") (pin "2") (pinfunction "2_2") (pintype "passive"))
    )
    (net (code "24") (name "Net-(D8-A)") (class "Default")
      (node (ref "D8") (pin "1") (pinfunction "A_1") (pintype "passive"))
      (node (ref "Q4") (pin "3") (pinfunction "D_3") (pintype "passive"))
      (node (ref "R15") (pin "1") (pinfunction "1_1") (pintype "passive"))
      (node (ref "U5") (pin "2") (pinfunction "-_2") (pintype "passive"))
    )
    (net (code "25") (name "Net-(D9-A)") (class "Default")
      (node (ref "D9") (pin "1") (pinfunction "A_1") (pintype "passive"))
      (node (ref "Q3") (pin "3") (pinfunction "D_3") (pintype "passive"))
      (node (ref "R16") (pin "1") (pinfunction "1_1") (pintype "passive"))
      (node (ref "U6") (pin "2") (pinfunction "-_2") (pintype "passive"))
    )
    (net (code "26") (name "Net-(D10-K)") (class "Default")
      (node (ref "D10") (pin "2") (pinfunction "K_2") (pintype "passive"))
      (node (ref "R21") (pin "1") (pinfunction "1_1") (pintype "passive"))
    )
    (net (code "27") (name "Net-(D11-A)") (class "Default")
      (node (ref "D11") (pin "1") (pinfunction "A_1") (pintype "passive"))
      (node (ref "R28") (pin "2") (pinfunction "2_2") (pintype "passive"))
    )
    (net (code "28") (name "Net-(Q1-G)") (class "Default")
      (node (ref "Q1") (pin "1") (pinfunction "G_1") (pintype "passive"))
      (node (ref "R5") (pin "2") (pinfunction "2_2") (pintype "passive"))
      (node (ref "R7") (pin "2") (pinfunction "2_2") (pintype "passive"))
    )
    (net (code "29") (name "Net-(Q2-G)") (class "Default")
      (node (ref "Q2") (pin "1") (pinfunction "G_1") (pintype "passive"))
      (node (ref "R10") (pin "2") (pinfunction "2_2") (pintype "passive"))
      (node (ref "R11") (pin "2") (pinfunction "2_2") (pintype "passive"))
    )
    (net (code "30") (name "Net-(Q3-G)") (class "Default")
      (node (ref "Q3") (pin "1") (pinfunction "G_1") (pintype "passive"))
      (node (ref "R17") (pin "2") (pinfunction "2_2") (pintype "passive"))
      (node (ref "R19") (pin "2") (pinfunction "2_2") (pintype "passive"))
    )
    (net (code "31") (name "Net-(Q4-G)") (class "Default")
      (node (ref "Q4") (pin "1") (pinfunction "G_1") (pintype "passive"))
      (node (ref "R18") (pin "2") (pinfunction "2_2") (pintype "passive"))
      (node (ref "R20") (pin "2") (pinfunction "2_2") (pintype "passive"))
    )
    (net (code "32") (name "Net-(TP1-TP)") (class "Default")
      (node (ref "R22") (pin "2") (pinfunction "2_2") (pintype "passive"))
      (node (ref "TP1") (pin "1") (pinfunction "TP_1") (pintype "passive"))
      (node (ref "U8") (pin "13") (pinfunction "/INT_13") (pintype "output"))
    )
    (net (code "33") (name "Net-(TP3-TP)") (class "Default")
      (node (ref "TP3") (pin "1") (pinfunction "TP_1") (pintype "passive"))
      (node (ref "U9") (pin "8") (pinfunction "EOC_8") (pintype "output"))
    )
    (net (code "34") (name "Net-(U2-BST)") (class "Default")
      (node (ref "C2") (pin "2") (pinfunction "2_2") (pintype "passive"))
      (node (ref "U2") (pin "4") (pinfunction "BST_4") (pintype "passive"))
    )
    (net (code "35") (name "Net-(U2-EN)") (class "Default")
      (node (ref "R4") (pin "1") (pinfunction "1_1") (pintype "passive"))
      (node (ref "U2") (pin "5") (pinfunction "EN_5") (pintype "passive"))
    )
    (net (code "36") (name "Net-(U2-FB)") (class "Default")
      (node (ref "C7") (pin "1") (pinfunction "1_1") (pintype "passive"))
      (node (ref "R6") (pin "1") (pinfunction "1_1") (pintype "passive"))
      (node (ref "R9") (pin "2") (pinfunction "2_2") (pintype "passive"))
      (node (ref "U2") (pin "6") (pinfunction "FB_6") (pintype "passive"))
    )
    (net (code "37") (name "Net-(U2-SW)") (class "Default")
      (node (ref "C2") (pin "1") (pinfunction "1_1") (pintype "passive"))
      (node (ref "L1") (pin "1") (pinfunction "1_1") (pintype "passive"))
      (node (ref "U2") (pin "2") (pinfunction "SW_2") (pintype "passive"))
    )
    (net (code "38") (name "Net-(U4-BST)") (class "Default")
      (node (ref "C12") (pin "2") (pinfunction "2_2") (pintype "passive"))
      (node (ref "U4") (pin "4") (pinfunction "BST_4") (pintype "passive"))
    )
    (net (code "39") (name "Net-(U4-EN)") (class "Default")
      (node (ref "R12") (pin "1") (pinfunction "1_1") (pintype "passive"))
      (node (ref "U4") (pin "5") (pinfunction "EN_5") (pintype "passive"))
    )
    (net (code "40") (name "Net-(U4-FB)") (class "Default")
      (node (ref "C15") (pin "1") (pinfunction "1_1") (pintype "passive"))
      (node (ref "R13") (pin "1") (pinfunction "1_1") (pintype "passive"))
      (node (ref "R14") (pin "2") (pinfunction "2_2") (pintype "passive"))
      (node (ref "U4") (pin "6") (pinfunction "FB_6") (pintype "passive"))
    )
    (net (code "41") (name "Net-(U4-SW)") (class "Default")
      (node (ref "C12") (pin "1") (pinfunction "1_1") (pintype "passive"))
      (node (ref "L2") (pin "1") (pinfunction "1_1") (pintype "passive"))
      (node (ref "U4") (pin "2") (pinfunction "SW_2") (pintype "passive"))
    )
    (net (code "42") (name "Net-(U9-VDD)") (class "Default")
      (node (ref "JP1") (pin "1") (pinfunction "1_1") (pintype "passive"))
      (node (ref "U9") (pin "12") (pinfunction "VDD_12") (pintype "power_in"))
    )
    (net (code "43") (name "Net-(U9-VO+)") (class "Default")
      (node (ref "C26") (pin "2") (pinfunction "2_2") (pintype "passive"))
      (node (ref "U9") (pin "4") (pinfunction "VO+_4") (pintype "output"))
    )
    (net (code "44") (name "Net-(U9-VO-)") (class "Default")
      (node (ref "C26") (pin "1") (pinfunction "1_1") (pintype "passive"))
      (node (ref "U9") (pin "6") (pinfunction "VO-_6") (pintype "output"))
    )
    (net (code "45") (name "VIN") (class "Default")
      (node (ref "C13") (pin "2") (pinfunction "2_2") (pintype "passive"))
      (node (ref "C14") (pin "2") (pinfunction "2_2") (pintype "passive"))
      (node (ref "C5") (pin "2") (pinfunction "2_2") (pintype "passive"))
      (node (ref "C6") (pin "2") (pinfunction "2_2") (pintype "passive"))
      (node (ref "D3") (pin "2") (pinfunction "K_2") (pintype "passive"))
      (node (ref "R12") (pin "2") (pinfunction "2_2") (pintype "passive"))
      (node (ref "R4") (pin "2") (pinfunction "2_2") (pintype "passive"))
      (node (ref "U2") (pin "1") (pinfunction "IN_1") (pintype "power_in"))
      (node (ref "U4") (pin "1") (pinfunction "IN_1") (pintype "power_in"))
    )
    (net (code "46") (name "unconnected-(MH1-GND-Pad1)") (class "Default")
      (node (ref "MH1") (pin "1") (pinfunction "GND_1") (pintype "passive+no_connect"))
    )
    (net (code "47") (name "unconnected-(MH2-GND-Pad1)") (class "Default")
      (node (ref "MH2") (pin "1") (pinfunction "GND_1") (pintype "passive+no_connect"))
    )
    (net (code "48") (name "unconnected-(MH3-GND-Pad1)") (class "Default")
      (node (ref "MH3") (pin "1") (pinfunction "GND_1") (pintype "passive+no_connect"))
    )
    (net (code "49") (name "unconnected-(MH4-GND-Pad1)") (class "Default")
      (node (ref "MH4") (pin "1") (pinfunction "GND_1") (pintype "passive+no_connect"))
    )
    (net (code "50") (name "unconnected-(U9-MISO-Pad7)") (class "Default")
      (node (ref "U9") (pin "7") (pinfunction "MISO_7") (pintype "output+no_connect"))
    )
    (net (code "51") (name "unconnected-(U9-SS-Pad1)") (class "Default")
      (node (ref "U9") (pin "1") (pinfunction "SS_1") (pintype "input+no_connect"))
    )
  )
)
